# micro.net
KiCad netlist of a schematic drawn in Altium Designer
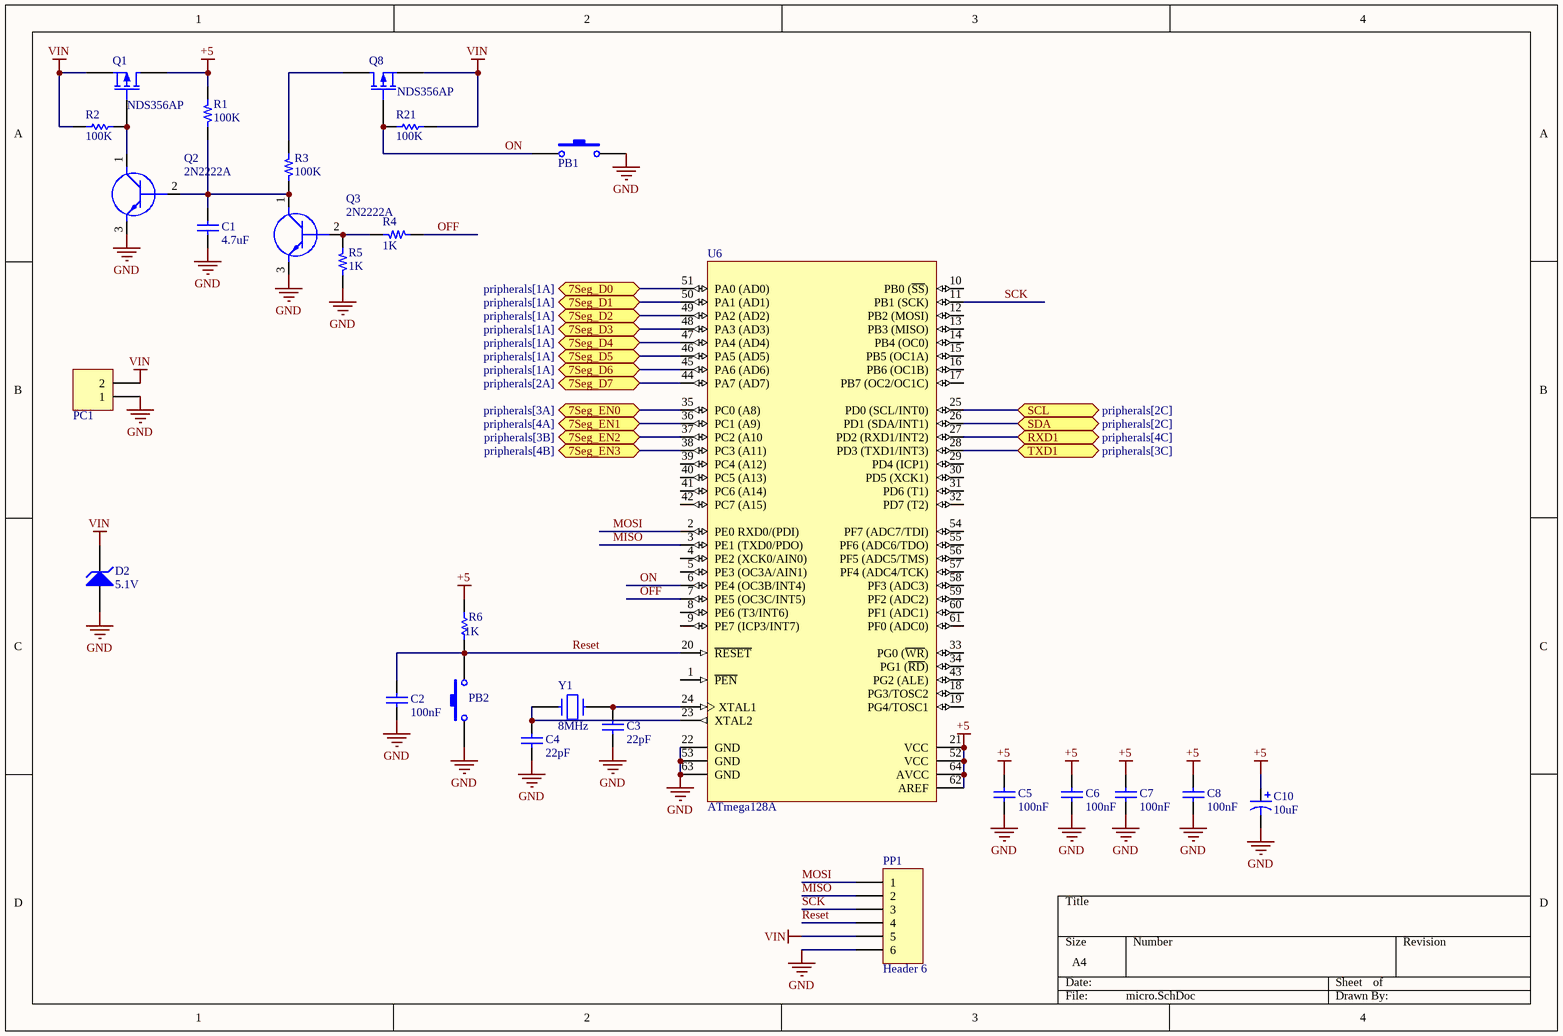
[diagram p0: micro.SchDoc]

(export (version "E")
  (design (tool "Eeschema 10.0.6"))
  (components
    (comp (ref "C1")
      (value "4.7uF")
      (footprint "CAP0805")
      (description "CAP seramic")
      (fields (field (name "Comment") "cap 4.7uF"))
      (libsource (lib "Altium library (www.AVRelec.com)") (part "Cap ceramic"))
    )
    (comp (ref "C2")
      (value "100nF")
      (footprint "CAP0805")
      (description "CAP seramic")
      (fields (field (name "Comment") "cap 100nF"))
      (libsource (lib "Altium library (www.AVRelec.com)") (part "Cap ceramic"))
    )
    (comp (ref "C3")
      (value "22pF")
      (footprint "CAP0805")
      (description "CAP seramic")
      (fields (field (name "Comment") "cap 22pF"))
      (libsource (lib "Altium library (www.AVRelec.com)") (part "Cap ceramic"))
    )
    (comp (ref "C4")
      (value "22pF")
      (footprint "CAP0805")
      (description "CAP seramic")
      (fields (field (name "Comment") "cap 22pF"))
      (libsource (lib "Altium library (www.AVRelec.com)") (part "Cap ceramic"))
    )
    (comp (ref "C5")
      (value "100nF")
      (footprint "CAP0805")
      (description "CAP seramic")
      (fields (field (name "Comment") "cap 100nF"))
      (libsource (lib "Altium library (www.AVRelec.com)") (part "Cap ceramic"))
    )
    (comp (ref "C6")
      (value "100nF")
      (footprint "CAP0805")
      (description "CAP seramic")
      (fields (field (name "Comment") "cap 100nF"))
      (libsource (lib "Altium library (www.AVRelec.com)") (part "Cap ceramic"))
    )
    (comp (ref "C7")
      (value "100nF")
      (footprint "CAP0805")
      (description "CAP seramic")
      (fields (field (name "Comment") "cap 100nF"))
      (libsource (lib "Altium library (www.AVRelec.com)") (part "Cap ceramic"))
    )
    (comp (ref "C8")
      (value "100nF")
      (footprint "CAP0805")
      (description "CAP seramic")
      (fields (field (name "Comment") "cap 100nF"))
      (libsource (lib "Altium library (www.AVRelec.com)") (part "Cap ceramic"))
    )
    (comp (ref "C10")
      (value "10uF")
      (footprint "CAP0805")
      (description "CAP seramic")
      (fields (field (name "Comment") "cap 10uF") (field (name "PUBLISHER") "Altium Limited"))
      (libsource (lib "Miscellaneous Devices") (part "Cap Pol1"))
    )
    (comp (ref "D2")
      (value "5.1V")
      (footprint "Diode 1n4148 SMD")
      (description "Zener Diode 5.1v")
      (fields (field (name "PUBLISHER") "Altium Limited"))
      (libsource (lib "Miscellaneous Devices") (part "D Zener"))
    )
    (comp (ref "PB1")
      (value "Push-Button-tall")
      (footprint "tact-12mm")
      (libsource (lib "Mine-Discreet") (part "Push-Button-tall"))
    )
    (comp (ref "PB2")
      (value "Push-Button-tall")
      (footprint "tack-sw-3x5x6")
      (libsource (lib "Mine-Discreet") (part "Push-Button-tall"))
    )
    (comp (ref "PC1")
      (value "Power Connector")
      (footprint "My_ Power_Connector")
      (description "white Power Connector")
      (libsource (lib "Altium library (www.AVRelec.com)") (part "Power Connector"))
    )
    (comp (ref "PP1")
      (value "Header 6")
      (footprint "HDR1X6")
      (description "Header, 6-Pin , female")
      (fields (field (name "PUBLISHER") "Altium Limited"))
      (libsource (lib "Miscellaneous Connectors") (part "Header 6"))
    )
    (comp (ref "Q1")
      (value "NDS356AP")
      (footprint "soT95p280x130-3n")
      (description "P-Channel MOSFET SOT23")
      (fields (field (name "PUBLISHER") "Altium Limited"))
      (libsource (lib "Miscellaneous Devices") (part "MOSFET-P"))
    )
    (comp (ref "Q2")
      (value "2N2222A")
      (footprint "soT95p280x130-3n")
      (description "Transistor BJT NPN SMD")
      (libsource (lib "*") (part "2N2222A"))
    )
    (comp (ref "Q3")
      (value "2N2222A")
      (footprint "soT95p280x130-3n")
      (description "Transistor BJT NPN SMD")
      (libsource (lib "*") (part "2N2222A"))
    )
    (comp (ref "Q8")
      (value "NDS356AP")
      (footprint "soT95p280x130-3n")
      (description "P-Channel MOSFET SOT23")
      (fields (field (name "PUBLISHER") "Altium Limited"))
      (libsource (lib "Miscellaneous Devices") (part "MOSFET-P"))
    )
    (comp (ref "R1")
      (value "100K")
      (footprint "RES0805")
      (description "RES SMD 0603")
      (fields (field (name "PART NUMBER") "RCS0805100KFKEA"))
      (libsource (lib "lamp control-ver2") (part "Resistor"))
    )
    (comp (ref "R2")
      (value "100K")
      (footprint "RES0805")
      (description "Resistor")
      (fields (field (name "Comment") "Res 100K") (field (name "PUBLISHER") "Altium Limited"))
      (libsource (lib "Miscellaneous Devices") (part "Res1"))
    )
    (comp (ref "R3")
      (value "100K")
      (footprint "RES0805")
      (description "RES SMD 0603")
      (fields (field (name "PART NUMBER") "RCS0805100KFKEA"))
      (libsource (lib "lamp control-ver2") (part "Resistor"))
    )
    (comp (ref "R4")
      (value "1K")
      (footprint "RES0805")
      (description "RES SMD 0603")
      (fields (field (name "PART NUMBER") "RCS0805100KFKEA"))
      (libsource (lib "lamp control-ver2") (part "Resistor"))
    )
    (comp (ref "R5")
      (value "1K")
      (footprint "RES0805")
      (description "RES SMD 0603")
      (fields (field (name "PART NUMBER") "RCS0805100KFKEA"))
      (libsource (lib "lamp control-ver2") (part "Resistor"))
    )
    (comp (ref "R6")
      (value "1K")
      (footprint "RES0805")
      (description "Resistor")
      (fields (field (name "Comment") "Res 1K") (field (name "PUBLISHER") "Altium Limited"))
      (libsource (lib "Miscellaneous Devices") (part "Res1"))
    )
    (comp (ref "R21")
      (value "100K")
      (footprint "RES0805")
      (description "Resistor")
      (fields (field (name "Comment") "Res 100K") (field (name "PUBLISHER") "Altium Limited"))
      (libsource (lib "Miscellaneous Devices") (part "Res1"))
    )
    (comp (ref "U6")
      (value "ATmega128A")
      (footprint "TQFP64_N")
      (fields (field (name "PUBLISHER") "Altium Limited"))
      (libsource (lib "Altium (2)") (part "ATmega128A"))
    )
    (comp (ref "Y1")
      (value "8MHz")
      (footprint "My_Crystal")
      (description "Crystal")
      (libsource (lib "Altium library (www.AVRelec.com)") (part "CRYSTAL"))
    )
  )
  (nets
    (net (code "1") (name "+5") (class "Default")
      (node (ref "C10") (pin "1") (pinfunction "1_1") (pintype "passive"))
      (node (ref "C5") (pin "2") (pinfunction "2_2") (pintype "passive"))
      (node (ref "C6") (pin "2") (pinfunction "2_2") (pintype "passive"))
      (node (ref "C7") (pin "2") (pinfunction "2_2") (pintype "passive"))
      (node (ref "C8") (pin "2") (pinfunction "2_2") (pintype "passive"))
      (node (ref "Q1") (pin "1") (pinfunction "D_1") (pintype "passive"))
      (node (ref "R1") (pin "1") (pinfunction "1_1") (pintype "passive"))
      (node (ref "R6") (pin "1") (pinfunction "1_1") (pintype "passive"))
      (node (ref "U6") (pin "21") (pinfunction "VCC_21") (pintype "power_in"))
      (node (ref "U6") (pin "52") (pinfunction "VCC_52") (pintype "power_in"))
      (node (ref "U6") (pin "62") (pinfunction "AREF_62") (pintype "power_in"))
      (node (ref "U6") (pin "64") (pinfunction "AVCC_64") (pintype "power_in"))
    )
    (net (code "2") (name "/7Seg_D0") (class "Default")
      (node (ref "U6") (pin "51") (pinfunction "PA0_(AD0)_51") (pintype "bidirectional"))
    )
    (net (code "3") (name "/7Seg_D1") (class "Default")
      (node (ref "U6") (pin "50") (pinfunction "PA1_(AD1)_50") (pintype "bidirectional"))
    )
    (net (code "4") (name "/7Seg_D2") (class "Default")
      (node (ref "U6") (pin "49") (pinfunction "PA2_(AD2)_49") (pintype "bidirectional"))
    )
    (net (code "5") (name "/7Seg_D3") (class "Default")
      (node (ref "U6") (pin "48") (pinfunction "PA3_(AD3)_48") (pintype "bidirectional"))
    )
    (net (code "6") (name "/7Seg_D4") (class "Default")
      (node (ref "U6") (pin "47") (pinfunction "PA4_(AD4)_47") (pintype "bidirectional"))
    )
    (net (code "7") (name "/7Seg_D5") (class "Default")
      (node (ref "U6") (pin "46") (pinfunction "PA5_(AD5)_46") (pintype "bidirectional"))
    )
    (net (code "8") (name "/7Seg_D6") (class "Default")
      (node (ref "U6") (pin "45") (pinfunction "PA6_(AD6)_45") (pintype "bidirectional"))
    )
    (net (code "9") (name "/7Seg_D7") (class "Default")
      (node (ref "U6") (pin "44") (pinfunction "PA7_(AD7)_44") (pintype "bidirectional"))
    )
    (net (code "10") (name "/7Seg_EN0") (class "Default")
      (node (ref "U6") (pin "35") (pinfunction "PC0_(A8)_35") (pintype "bidirectional"))
    )
    (net (code "11") (name "/7Seg_EN1") (class "Default")
      (node (ref "U6") (pin "36") (pinfunction "PC1_(A9)_36") (pintype "bidirectional"))
    )
    (net (code "12") (name "/7Seg_EN2") (class "Default")
      (node (ref "U6") (pin "37") (pinfunction "PC2_(A10_37") (pintype "bidirectional"))
    )
    (net (code "13") (name "/7Seg_EN3") (class "Default")
      (node (ref "U6") (pin "38") (pinfunction "PC3_(A11)_38") (pintype "bidirectional"))
    )
    (net (code "14") (name "/MISO") (class "Default")
      (node (ref "PP1") (pin "2") (pinfunction "2_2") (pintype "passive"))
      (node (ref "U6") (pin "3") (pinfunction "PE1_(TXD0/PDO)_3") (pintype "bidirectional"))
    )
    (net (code "15") (name "/MOSI") (class "Default")
      (node (ref "PP1") (pin "1") (pinfunction "1_1") (pintype "passive"))
      (node (ref "U6") (pin "2") (pinfunction "PE0_RXD0/(PDI)_2") (pintype "bidirectional"))
    )
    (net (code "16") (name "/OFF") (class "Default")
      (node (ref "R4") (pin "1") (pinfunction "1_1") (pintype "passive"))
      (node (ref "U6") (pin "7") (pinfunction "PE5_(OC3C/INT5)_7") (pintype "bidirectional"))
    )
    (net (code "17") (name "/ON") (class "Default")
      (node (ref "PB1") (pin "1") (pinfunction "1_1") (pintype "passive"))
      (node (ref "Q8") (pin "2") (pinfunction "G_2") (pintype "passive"))
      (node (ref "R21") (pin "2") (pinfunction "2_2") (pintype "passive"))
      (node (ref "U6") (pin "6") (pinfunction "PE4_(OC3B/INT4)_6") (pintype "bidirectional"))
    )
    (net (code "18") (name "/RXD1") (class "Default")
      (node (ref "U6") (pin "27") (pinfunction "PD2_(RXD1/INT2)_27") (pintype "bidirectional"))
    )
    (net (code "19") (name "/Reset") (class "Default")
      (node (ref "C2") (pin "2") (pinfunction "2_2") (pintype "passive"))
      (node (ref "PB2") (pin "2") (pinfunction "2_2") (pintype "passive"))
      (node (ref "PP1") (pin "4") (pinfunction "4_4") (pintype "passive"))
      (node (ref "R6") (pin "2") (pinfunction "2_2") (pintype "passive"))
      (node (ref "U6") (pin "20") (pinfunction "~{RESET}_20") (pintype "input"))
    )
    (net (code "20") (name "/SCK") (class "Default")
      (node (ref "PP1") (pin "3") (pinfunction "3_3") (pintype "passive"))
      (node (ref "U6") (pin "11") (pinfunction "PB1_(SCK)_11") (pintype "bidirectional"))
    )
    (net (code "21") (name "/SCL") (class "Default")
      (node (ref "U6") (pin "25") (pinfunction "PD0_(SCL/INT0)_25") (pintype "bidirectional"))
    )
    (net (code "22") (name "/SDA") (class "Default")
      (node (ref "U6") (pin "26") (pinfunction "PD1_(SDA/INT1)_26") (pintype "bidirectional"))
    )
    (net (code "23") (name "/TXD1") (class "Default")
      (node (ref "U6") (pin "28") (pinfunction "PD3_(TXD1/INT3)_28") (pintype "bidirectional"))
    )
    (net (code "24") (name "GND") (class "Default")
      (node (ref "C1") (pin "1") (pinfunction "1_1") (pintype "passive"))
      (node (ref "C10") (pin "2") (pinfunction "2_2") (pintype "passive"))
      (node (ref "C2") (pin "1") (pinfunction "1_1") (pintype "passive"))
      (node (ref "C3") (pin "1") (pinfunction "1_1") (pintype "passive"))
      (node (ref "C4") (pin "1") (pinfunction "1_1") (pintype "passive"))
      (node (ref "C5") (pin "1") (pinfunction "1_1") (pintype "passive"))
      (node (ref "C6") (pin "1") (pinfunction "1_1") (pintype "passive"))
      (node (ref "C7") (pin "1") (pinfunction "1_1") (pintype "passive"))
      (node (ref "C8") (pin "1") (pinfunction "1_1") (pintype "passive"))
      (node (ref "D2") (pin "1") (pinfunction "A_1") (pintype "passive"))
      (node (ref "PB1") (pin "2") (pinfunction "2_2") (pintype "passive"))
      (node (ref "PB2") (pin "1") (pinfunction "1_1") (pintype "passive"))
      (node (ref "PC1") (pin "1") (pinfunction "1_1") (pintype "passive"))
      (node (ref "PP1") (pin "6") (pinfunction "6_6") (pintype "passive"))
      (node (ref "Q2") (pin "3") (pinfunction "E_3") (pintype "passive"))
      (node (ref "Q3") (pin "3") (pinfunction "E_3") (pintype "passive"))
      (node (ref "R5") (pin "1") (pinfunction "1_1") (pintype "passive"))
      (node (ref "U6") (pin "22") (pinfunction "GND_22") (pintype "power_in"))
      (node (ref "U6") (pin "53") (pinfunction "GND_53") (pintype "power_in"))
      (node (ref "U6") (pin "63") (pinfunction "GND_63") (pintype "power_in"))
    )
    (net (code "25") (name "Net-(Q1-G)") (class "Default")
      (node (ref "Q1") (pin "2") (pinfunction "G_2") (pintype "passive"))
      (node (ref "Q2") (pin "1") (pinfunction "C_1") (pintype "passive"))
      (node (ref "R2") (pin "2") (pinfunction "2_2") (pintype "passive"))
    )
    (net (code "26") (name "Net-(Q2-B)") (class "Default")
      (node (ref "C1") (pin "2") (pinfunction "2_2") (pintype "passive"))
      (node (ref "Q2") (pin "2") (pinfunction "B_2") (pintype "passive"))
      (node (ref "Q3") (pin "1") (pinfunction "C_1") (pintype "passive"))
      (node (ref "R1") (pin "2") (pinfunction "2_2") (pintype "passive"))
      (node (ref "R3") (pin "2") (pinfunction "2_2") (pintype "passive"))
    )
    (net (code "27") (name "Net-(Q3-B)") (class "Default")
      (node (ref "Q3") (pin "2") (pinfunction "B_2") (pintype "passive"))
      (node (ref "R4") (pin "2") (pinfunction "2_2") (pintype "passive"))
      (node (ref "R5") (pin "2") (pinfunction "2_2") (pintype "passive"))
    )
    (net (code "28") (name "Net-(Q8-D)") (class "Default")
      (node (ref "Q8") (pin "1") (pinfunction "D_1") (pintype "passive"))
      (node (ref "R3") (pin "1") (pinfunction "1_1") (pintype "passive"))
    )
    (net (code "29") (name "Net-(U6-XTAL1)") (class "Default")
      (node (ref "C3") (pin "2") (pinfunction "2_2") (pintype "passive"))
      (node (ref "U6") (pin "24") (pinfunction "XTAL1_24") (pintype "input"))
      (node (ref "Y1") (pin "2") (pinfunction "2_2") (pintype "passive"))
    )
    (net (code "30") (name "Net-(U6-XTAL2)") (class "Default")
      (node (ref "C4") (pin "2") (pinfunction "2_2") (pintype "passive"))
      (node (ref "U6") (pin "23") (pinfunction "XTAL2_23") (pintype "output"))
      (node (ref "Y1") (pin "1") (pinfunction "1_1") (pintype "passive"))
    )
    (net (code "31") (name "VIN") (class "Default")
      (node (ref "D2") (pin "2") (pinfunction "K_2") (pintype "passive"))
      (node (ref "PC1") (pin "2") (pinfunction "2_2") (pintype "passive"))
      (node (ref "PP1") (pin "5") (pinfunction "5_5") (pintype "passive"))
      (node (ref "Q1") (pin "3") (pinfunction "S_3") (pintype "passive"))
      (node (ref "Q8") (pin "3") (pinfunction "S_3") (pintype "passive"))
      (node (ref "R2") (pin "1") (pinfunction "1_1") (pintype "passive"))
      (node (ref "R21") (pin "1") (pinfunction "1_1") (pintype "passive"))
    )
    (net (code "32") (name "unconnected-(U6-PB0_(~{SS})-Pad10)") (class "Default")
      (node (ref "U6") (pin "10") (pinfunction "PB0_(~{SS})_10") (pintype "bidirectional"))
    )
    (net (code "33") (name "unconnected-(U6-PB2_(MOSI)-Pad12)") (class "Default")
      (node (ref "U6") (pin "12") (pinfunction "PB2_(MOSI)_12") (pintype "bidirectional"))
    )
    (net (code "34") (name "unconnected-(U6-PB3_(MISO)-Pad13)") (class "Default")
      (node (ref "U6") (pin "13") (pinfunction "PB3_(MISO)_13") (pintype "bidirectional"))
    )
    (net (code "35") (name "unconnected-(U6-PB4_(OC0)-Pad14)") (class "Default")
      (node (ref "U6") (pin "14") (pinfunction "PB4_(OC0)_14") (pintype "bidirectional"))
    )
    (net (code "36") (name "unconnected-(U6-PB5_(OC1A)-Pad15)") (class "Default")
      (node (ref "U6") (pin "15") (pinfunction "PB5_(OC1A)_15") (pintype "bidirectional"))
    )
    (net (code "37") (name "unconnected-(U6-PB6_(OC1B)-Pad16)") (class "Default")
      (node (ref "U6") (pin "16") (pinfunction "PB6_(OC1B)_16") (pintype "bidirectional"))
    )
    (net (code "38") (name "unconnected-(U6-PB7_(OC2{slash}OC1C)-Pad17)") (class "Default")
      (node (ref "U6") (pin "17") (pinfunction "PB7_(OC2/OC1C)_17") (pintype "bidirectional"))
    )
    (net (code "39") (name "unconnected-(U6-PC4_(A12)-Pad39)") (class "Default")
      (node (ref "U6") (pin "39") (pinfunction "PC4_(A12)_39") (pintype "bidirectional"))
    )
    (net (code "40") (name "unconnected-(U6-PC5_(A13)-Pad40)") (class "Default")
      (node (ref "U6") (pin "40") (pinfunction "PC5_(A13)_40") (pintype "bidirectional"))
    )
    (net (code "41") (name "unconnected-(U6-PC6_(A14)-Pad41)") (class "Default")
      (node (ref "U6") (pin "41") (pinfunction "PC6_(A14)_41") (pintype "bidirectional"))
    )
    (net (code "42") (name "unconnected-(U6-PC7_(A15)-Pad42)") (class "Default")
      (node (ref "U6") (pin "42") (pinfunction "PC7_(A15)_42") (pintype "bidirectional"))
    )
    (net (code "43") (name "unconnected-(U6-PD4_(ICP1)-Pad29)") (class "Default")
      (node (ref "U6") (pin "29") (pinfunction "PD4_(ICP1)_29") (pintype "bidirectional"))
    )
    (net (code "44") (name "unconnected-(U6-PD5_(XCK1)-Pad30)") (class "Default")
      (node (ref "U6") (pin "30") (pinfunction "PD5_(XCK1)_30") (pintype "bidirectional"))
    )
    (net (code "45") (name "unconnected-(U6-PD6_(T1)-Pad31)") (class "Default")
      (node (ref "U6") (pin "31") (pinfunction "PD6_(T1)_31") (pintype "bidirectional"))
    )
    (net (code "46") (name "unconnected-(U6-PD7_(T2)-Pad32)") (class "Default")
      (node (ref "U6") (pin "32") (pinfunction "PD7_(T2)_32") (pintype "bidirectional"))
    )
    (net (code "47") (name "unconnected-(U6-PE2_(XCK0{slash}AIN0)-Pad4)") (class "Default")
      (node (ref "U6") (pin "4") (pinfunction "PE2_(XCK0/AIN0)_4") (pintype "bidirectional"))
    )
    (net (code "48") (name "unconnected-(U6-PE3_(OC3A{slash}AIN1)-Pad5)") (class "Default")
      (node (ref "U6") (pin "5") (pinfunction "PE3_(OC3A/AIN1)_5") (pintype "bidirectional"))
    )
    (net (code "49") (name "unconnected-(U6-PE6_(T3{slash}INT6)-Pad8)") (class "Default")
      (node (ref "U6") (pin "8") (pinfunction "PE6_(T3/INT6)_8") (pintype "bidirectional"))
    )
    (net (code "50") (name "unconnected-(U6-PE7_(ICP3{slash}INT7)-Pad9)") (class "Default")
      (node (ref "U6") (pin "9") (pinfunction "PE7_(ICP3/INT7)_9") (pintype "bidirectional"))
    )
    (net (code "51") (name "unconnected-(U6-PF0_(ADC0)-Pad61)") (class "Default")
      (node (ref "U6") (pin "61") (pinfunction "PF0_(ADC0)_61") (pintype "bidirectional"))
    )
    (net (code "52") (name "unconnected-(U6-PF1_(ADC1)-Pad60)") (class "Default")
      (node (ref "U6") (pin "60") (pinfunction "PF1_(ADC1)_60") (pintype "bidirectional"))
    )
    (net (code "53") (name "unconnected-(U6-PF2_(ADC2)-Pad59)") (class "Default")
      (node (ref "U6") (pin "59") (pinfunction "PF2_(ADC2)_59") (pintype "bidirectional"))
    )
    (net (code "54") (name "unconnected-(U6-PF3_(ADC3)-Pad58)") (class "Default")
      (node (ref "U6") (pin "58") (pinfunction "PF3_(ADC3)_58") (pintype "bidirectional"))
    )
    (net (code "55") (name "unconnected-(U6-PF4_(ADC4{slash}TCK)-Pad57)") (class "Default")
      (node (ref "U6") (pin "57") (pinfunction "PF4_(ADC4/TCK)_57") (pintype "bidirectional"))
    )
    (net (code "56") (name "unconnected-(U6-PF5_(ADC5{slash}TMS)-Pad56)") (class "Default")
      (node (ref "U6") (pin "56") (pinfunction "PF5_(ADC5/TMS)_56") (pintype "bidirectional"))
    )
    (net (code "57") (name "unconnected-(U6-PF6_(ADC6{slash}TDO)-Pad55)") (class "Default")
      (node (ref "U6") (pin "55") (pinfunction "PF6_(ADC6/TDO)_55") (pintype "bidirectional"))
    )
    (net (code "58") (name "unconnected-(U6-PF7_(ADC7{slash}TDI)-Pad54)") (class "Default")
      (node (ref "U6") (pin "54") (pinfunction "PF7_(ADC7/TDI)_54") (pintype "bidirectional"))
    )
    (net (code "59") (name "unconnected-(U6-PG0_(~{WR})-Pad33)") (class "Default")
      (node (ref "U6") (pin "33") (pinfunction "PG0_(~{WR})_33") (pintype "bidirectional"))
    )
    (net (code "60") (name "unconnected-(U6-PG1_(~{RD})-Pad34)") (class "Default")
      (node (ref "U6") (pin "34") (pinfunction "PG1_(~{RD})_34") (pintype "bidirectional"))
    )
    (net (code "61") (name "unconnected-(U6-PG2_(ALE)-Pad43)") (class "Default")
      (node (ref "U6") (pin "43") (pinfunction "PG2_(ALE)_43") (pintype "bidirectional"))
    )
    (net (code "62") (name "unconnected-(U6-PG3{slash}TOSC2-Pad18)") (class "Default")
      (node (ref "U6") (pin "18") (pinfunction "PG3/TOSC2_18") (pintype "bidirectional"))
    )
    (net (code "63") (name "unconnected-(U6-PG4{slash}TOSC1-Pad19)") (class "Default")
      (node (ref "U6") (pin "19") (pinfunction "PG4/TOSC1_19") (pintype "bidirectional"))
    )
    (net (code "64") (name "unconnected-(U6-~{PEN}-Pad1)") (class "Default")
      (node (ref "U6") (pin "1") (pinfunction "~{PEN}_1") (pintype "input"))
    )
  )
)
